# FlashProgrammer03.net
KiCad netlist of a schematic drawn in EAGLE
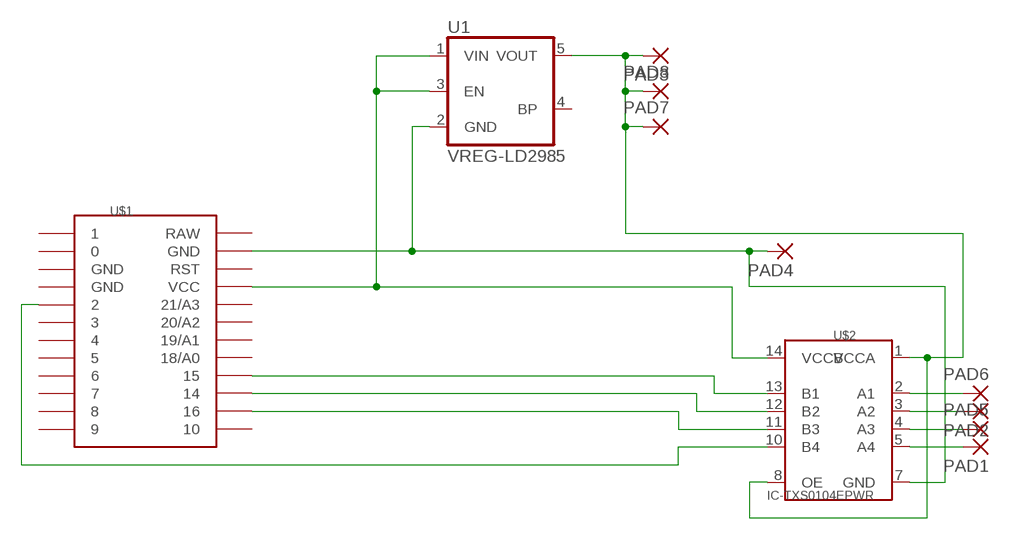
[diagram p0: schematic, sheet 1]

(export (version "E")
  (design (tool "Eeschema 10.0.6"))
  (components
    (comp (ref "PAD1")
      (value "1,6/0,8")
      (footprint "eagle-import:1,6_0,8")
      (libsource (lib "eagle-import") (part "1,6/0,8"))
    )
    (comp (ref "PAD2")
      (value "1,6/0,8")
      (footprint "eagle-import:1,6_0,8")
      (libsource (lib "eagle-import") (part "1,6/0,8"))
    )
    (comp (ref "PAD3")
      (value "1,6/0,8")
      (footprint "eagle-import:1,6_0,8")
      (libsource (lib "eagle-import") (part "1,6/0,8"))
    )
    (comp (ref "PAD4")
      (value "1,6/0,8")
      (footprint "eagle-import:1,6_0,8")
      (libsource (lib "eagle-import") (part "1,6/0,8"))
    )
    (comp (ref "PAD5")
      (value "1,6/0,8")
      (footprint "eagle-import:1,6_0,8")
      (libsource (lib "eagle-import") (part "1,6/0,8"))
    )
    (comp (ref "PAD6")
      (value "1,6/0,8")
      (footprint "eagle-import:1,6_0,8")
      (libsource (lib "eagle-import") (part "1,6/0,8"))
    )
    (comp (ref "PAD7")
      (value "1,6/0,8")
      (footprint "eagle-import:1,6_0,8")
      (libsource (lib "eagle-import") (part "1,6/0,8"))
    )
    (comp (ref "PAD8")
      (value "1,6/0,8")
      (footprint "eagle-import:1,6_0,8")
      (libsource (lib "eagle-import") (part "1,6/0,8"))
    )
    (comp (ref "U$1")
      (value "PROMICRO")
      (footprint "eagle-import:PROMICRO")
      (libsource (lib "eagle-import") (part "PROMICRO"))
    )
    (comp (ref "U$2")
      (value "IC-TXS0104EPWR")
      (footprint "eagle-import:TSSOP14")
      (libsource (lib "eagle-import") (part "IC-TXS0104EPWR"))
    )
    (comp (ref "U1")
      (value "VREG-LD2985")
      (footprint "eagle-import:SOT95P280X145-5")
      (libsource (lib "eagle-import") (part "VREG-LD2985"))
    )
  )
  (nets
    (net (code "1") (name "/0") (class "Default")
      (node (ref "U$1") (pin "0") (pinfunction "0_0") (pintype "power_in"))
    )
    (net (code "2") (name "/1") (class "Default")
      (node (ref "U$1") (pin "1") (pinfunction "1_1") (pintype "power_in"))
    )
    (net (code "3") (name "/GND") (class "Default")
      (node (ref "U$1") (pin "GND@2") (pinfunction "GND_GND@2") (pintype "power_in"))
    )
    (net (code "4") (name "/RAW") (class "Default")
      (node (ref "U$1") (pin "RAW") (pinfunction "RAW_RAW") (pintype "power_in"))
    )
    (net (code "5") (name "Net-(PAD1-P)") (class "Default")
      (node (ref "PAD1") (pin "1") (pinfunction "P_1") (pintype "passive"))
      (node (ref "U$2") (pin "5") (pinfunction "A4_5") (pintype "bidirectional"))
    )
    (net (code "6") (name "Net-(PAD2-P)") (class "Default")
      (node (ref "PAD2") (pin "1") (pinfunction "P_1") (pintype "passive"))
      (node (ref "U$2") (pin "3") (pinfunction "A2_3") (pintype "bidirectional"))
    )
    (net (code "7") (name "Net-(PAD3-P)") (class "Default")
      (node (ref "PAD3") (pin "1") (pinfunction "P_1") (pintype "passive"))
      (node (ref "PAD7") (pin "1") (pinfunction "P_1") (pintype "passive"))
      (node (ref "PAD8") (pin "1") (pinfunction "P_1") (pintype "passive"))
      (node (ref "U$2") (pin "1") (pinfunction "VCCA_1") (pintype "bidirectional"))
      (node (ref "U$2") (pin "8") (pinfunction "OE_8") (pintype "bidirectional"))
      (node (ref "U1") (pin "5") (pinfunction "VOUT_5") (pintype "passive"))
    )
    (net (code "8") (name "Net-(PAD4-P)") (class "Default")
      (node (ref "PAD4") (pin "1") (pinfunction "P_1") (pintype "passive"))
      (node (ref "U$1") (pin "GND@1") (pinfunction "GND_GND@1") (pintype "power_in"))
      (node (ref "U$2") (pin "7") (pinfunction "GND_7") (pintype "bidirectional"))
      (node (ref "U1") (pin "2") (pinfunction "GND_2") (pintype "passive"))
    )
    (net (code "9") (name "Net-(PAD5-P)") (class "Default")
      (node (ref "PAD5") (pin "1") (pinfunction "P_1") (pintype "passive"))
      (node (ref "U$2") (pin "4") (pinfunction "A3_4") (pintype "bidirectional"))
    )
    (net (code "10") (name "Net-(PAD6-P)") (class "Default")
      (node (ref "PAD6") (pin "1") (pinfunction "P_1") (pintype "passive"))
      (node (ref "U$2") (pin "2") (pinfunction "A1_2") (pintype "bidirectional"))
    )
    (net (code "11") (name "Net-(U$2-B1)") (class "Default")
      (node (ref "U$1") (pin "15") (pinfunction "15_15") (pintype "bidirectional"))
      (node (ref "U$2") (pin "13") (pinfunction "B1_13") (pintype "bidirectional"))
    )
    (net (code "12") (name "Net-(U$2-B2)") (class "Default")
      (node (ref "U$1") (pin "14") (pinfunction "14_14") (pintype "bidirectional"))
      (node (ref "U$2") (pin "12") (pinfunction "B2_12") (pintype "bidirectional"))
    )
    (net (code "13") (name "Net-(U$2-B3)") (class "Default")
      (node (ref "U$1") (pin "16") (pinfunction "16_16") (pintype "bidirectional"))
      (node (ref "U$2") (pin "11") (pinfunction "B3_11") (pintype "bidirectional"))
    )
    (net (code "14") (name "Net-(U$2-B4)") (class "Default")
      (node (ref "U$1") (pin "2") (pinfunction "2_2") (pintype "bidirectional"))
      (node (ref "U$2") (pin "10") (pinfunction "B4_10") (pintype "bidirectional"))
    )
    (net (code "15") (name "Net-(U$2-VCCB)") (class "Default")
      (node (ref "U$1") (pin "VCC") (pinfunction "VCC_VCC") (pintype "power_in"))
      (node (ref "U$2") (pin "14") (pinfunction "VCCB_14") (pintype "bidirectional"))
      (node (ref "U1") (pin "1") (pinfunction "VIN_1") (pintype "input"))
      (node (ref "U1") (pin "3") (pinfunction "EN_3") (pintype "input"))
    )
    (net (code "16") (name "unconnected-(U$1-GND-PadGND@3)") (class "Default")
      (node (ref "U$1") (pin "GND@3") (pinfunction "GND_GND@3") (pintype "bidirectional"))
    )
    (net (code "17") (name "unconnected-(U$1-Pad3)") (class "Default")
      (node (ref "U$1") (pin "3") (pinfunction "3_3") (pintype "bidirectional"))
    )
    (net (code "18") (name "unconnected-(U$1-Pad4)") (class "Default")
      (node (ref "U$1") (pin "4") (pinfunction "4_4") (pintype "bidirectional"))
    )
    (net (code "19") (name "unconnected-(U$1-Pad5)") (class "Default")
      (node (ref "U$1") (pin "5") (pinfunction "5_5") (pintype "bidirectional"))
    )
    (net (code "20") (name "unconnected-(U$1-Pad6)") (class "Default")
      (node (ref "U$1") (pin "6") (pinfunction "6_6") (pintype "bidirectional"))
    )
    (net (code "21") (name "unconnected-(U$1-Pad7)") (class "Default")
      (node (ref "U$1") (pin "7") (pinfunction "7_7") (pintype "bidirectional"))
    )
    (net (code "22") (name "unconnected-(U$1-Pad8)") (class "Default")
      (node (ref "U$1") (pin "8") (pinfunction "8_8") (pintype "bidirectional"))
    )
    (net (code "23") (name "unconnected-(U$1-Pad9)") (class "Default")
      (node (ref "U$1") (pin "9") (pinfunction "9_9") (pintype "bidirectional"))
    )
    (net (code "24") (name "unconnected-(U$1-Pad10)") (class "Default")
      (node (ref "U$1") (pin "10") (pinfunction "10_10") (pintype "bidirectional"))
    )
    (net (code "25") (name "unconnected-(U$1-Pad18{slash}A0)") (class "Default")
      (node (ref "U$1") (pin "18/A0") (pinfunction "18/A0_18/A0") (pintype "bidirectional"))
    )
    (net (code "26") (name "unconnected-(U$1-Pad19{slash}A1)") (class "Default")
      (node (ref "U$1") (pin "19/A1") (pinfunction "19/A1_19/A1") (pintype "bidirectional"))
    )
    (net (code "27") (name "unconnected-(U$1-Pad20{slash}A2)") (class "Default")
      (node (ref "U$1") (pin "20/A2") (pinfunction "20/A2_20/A2") (pintype "bidirectional"))
    )
    (net (code "28") (name "unconnected-(U$1-Pad21{slash}A3)") (class "Default")
      (node (ref "U$1") (pin "21/A3") (pinfunction "21/A3_21/A3") (pintype "bidirectional"))
    )
    (net (code "29") (name "unconnected-(U$1-PadRST)") (class "Default")
      (node (ref "U$1") (pin "RST") (pinfunction "RST_RST") (pintype "bidirectional"))
    )
    (net (code "30") (name "unconnected-(U1-BP-Pad4)") (class "Default")
      (node (ref "U1") (pin "4") (pinfunction "BP_4") (pintype "input"))
    )
  )
)
